# schematic_Eload.net
KiCad netlist of a schematic drawn in Altium Designer
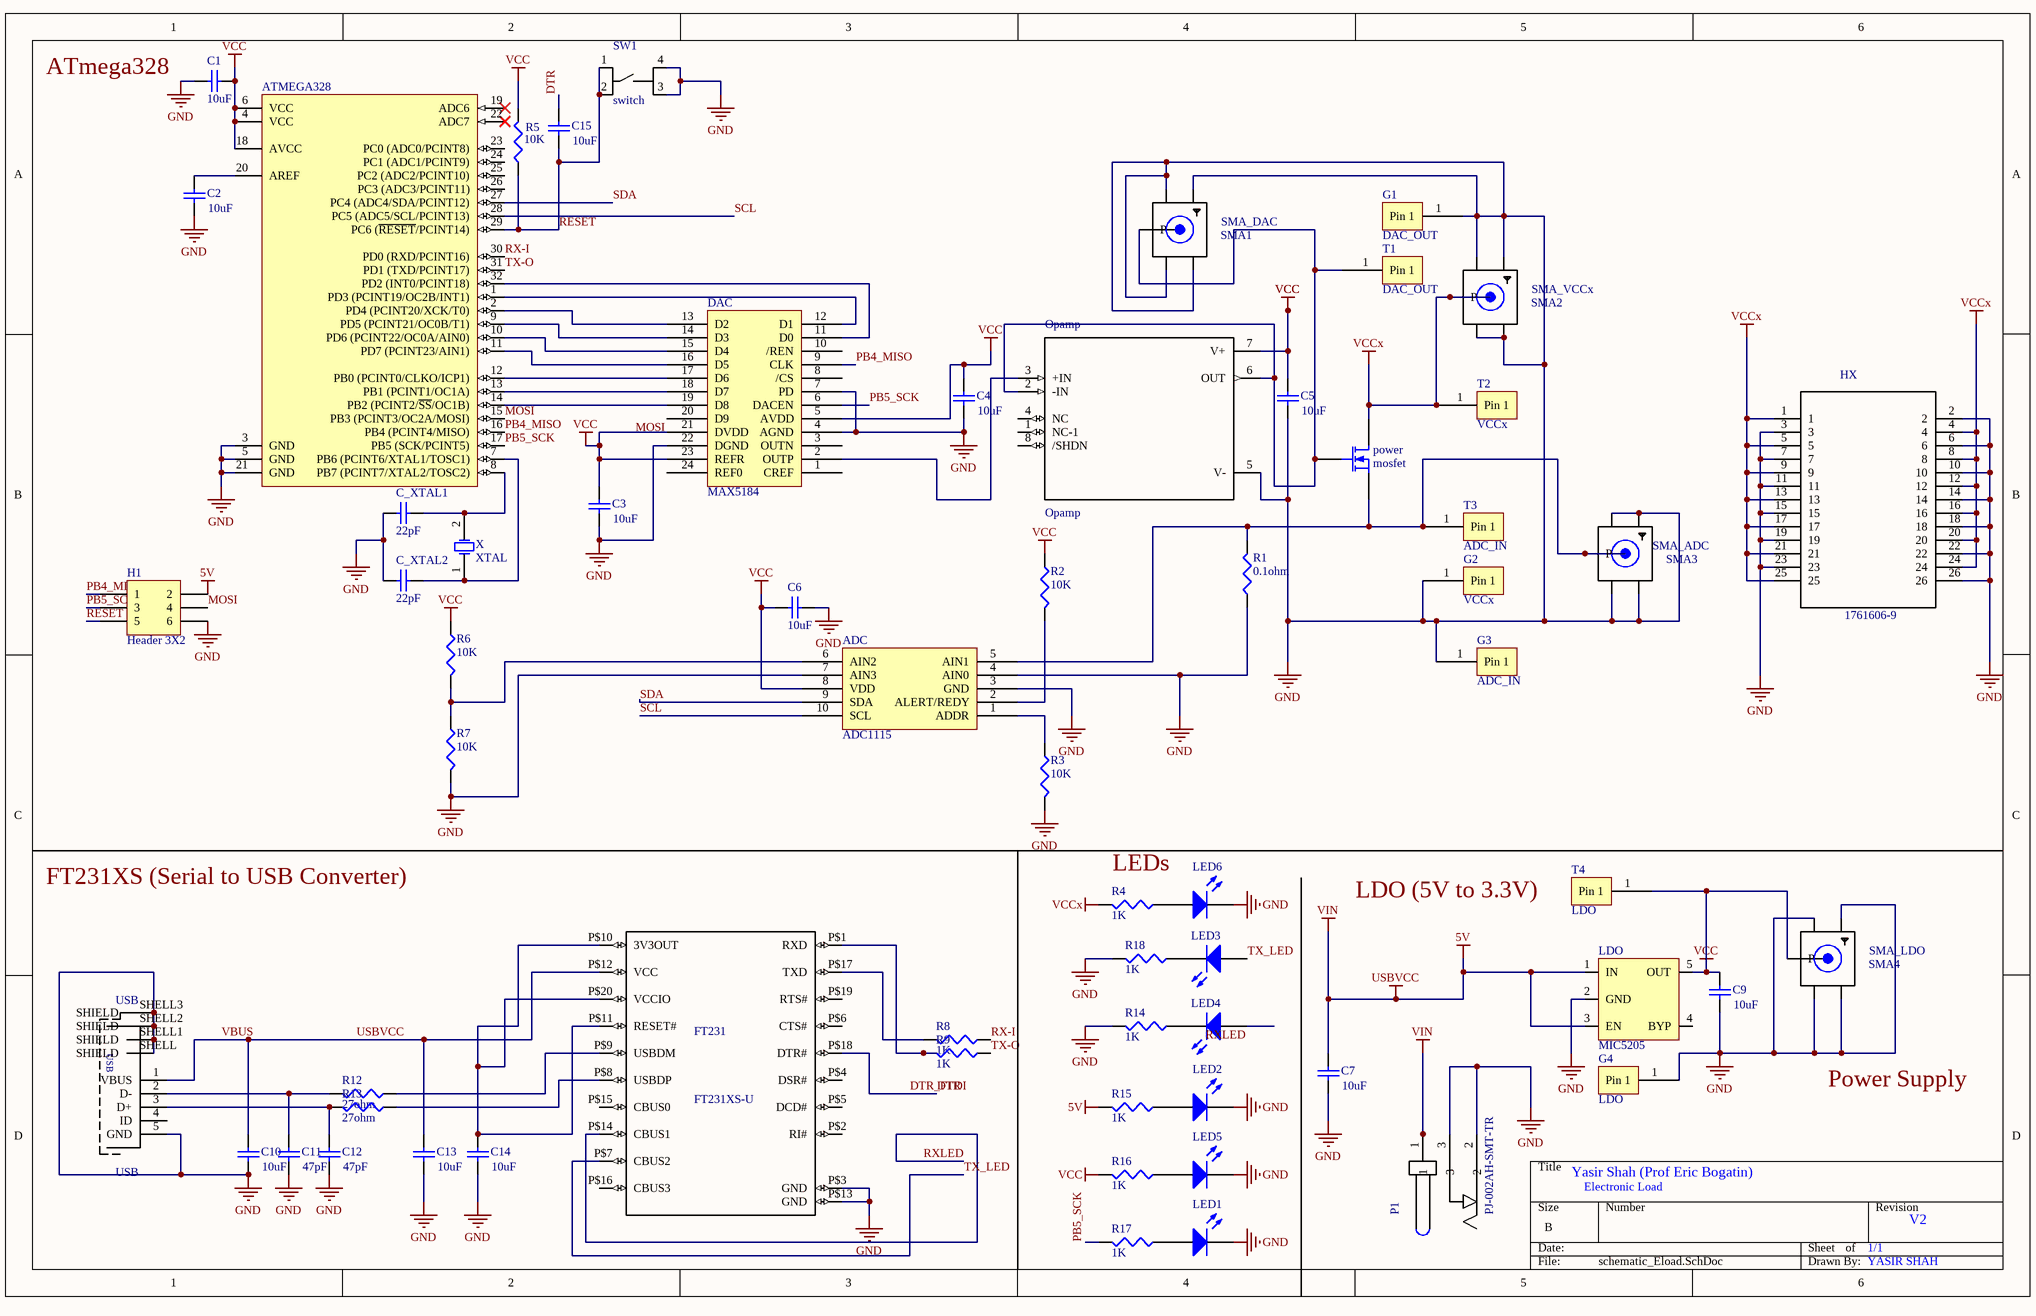
[diagram p0: schematic_Eload.SchDoc]

(export (version "E")
  (design (tool "Eeschema 10.0.6"))
  (components
    (comp (ref "ADC")
      (value "ADC1115")
      (footprint "MSOP10")
      (libsource (lib "Schematic_Library") (part "ADC"))
    )
    (comp (ref "ATMEGA328")
      (value "ATmega328-AU")
      (footprint "QFP32P80_900X900X120L60X37N")
      (fields (field (name "PUBLISHER") "Altium Limited"))
      (libsource (lib "Atmel Microcontroller 8-Bit megaAVR") (part "ATmega328-AU"))
    )
    (comp (ref "C1")
      (value "10uF")
      (footprint "CAPC2012X140N")
      (description "Capacitor (Semiconductor SIM Model)")
      (fields (field (name "Comment") "Cap Semi") (field (name "PUBLISHER") "Altium Limited"))
      (libsource (lib "Miscellaneous Devices") (part "Cap Semi"))
    )
    (comp (ref "C2")
      (value "10uF")
      (footprint "CAPC2012X140N")
      (description "Capacitor (Semiconductor SIM Model)")
      (fields (field (name "Comment") "Cap Semi") (field (name "PUBLISHER") "Altium Limited"))
      (libsource (lib "Miscellaneous Devices") (part "Cap Semi"))
    )
    (comp (ref "C3")
      (value "10uF")
      (footprint "CAPC2012X140N")
      (description "Capacitor (Semiconductor SIM Model)")
      (fields (field (name "Comment") "Cap Semi") (field (name "PUBLISHER") "Altium Limited"))
      (libsource (lib "Miscellaneous Devices") (part "Cap Semi"))
    )
    (comp (ref "C4")
      (value "10uF")
      (footprint "CAPC2012X140N")
      (description "Capacitor (Semiconductor SIM Model)")
      (fields (field (name "Comment") "Cap Semi") (field (name "PUBLISHER") "Altium Limited"))
      (libsource (lib "Miscellaneous Devices") (part "Cap Semi"))
    )
    (comp (ref "C5")
      (value "10uF")
      (footprint "CAPC2012X140N")
      (description "Capacitor (Semiconductor SIM Model)")
      (fields (field (name "Comment") "Cap Semi") (field (name "PUBLISHER") "Altium Limited"))
      (libsource (lib "Miscellaneous Devices") (part "Cap Semi"))
    )
    (comp (ref "C6")
      (value "10uF")
      (footprint "CAPC2012X140N")
      (description "Capacitor (Semiconductor SIM Model)")
      (fields (field (name "Comment") "Cap Semi") (field (name "PUBLISHER") "Altium Limited"))
      (libsource (lib "Miscellaneous Devices") (part "Cap Semi"))
    )
    (comp (ref "C7")
      (value "10uF")
      (footprint "CAPC2012X140N")
      (description "Capacitor (Semiconductor SIM Model)")
      (fields (field (name "Comment") "Cap Semi") (field (name "PUBLISHER") "Altium Limited"))
      (libsource (lib "Miscellaneous Devices") (part "Cap Semi"))
    )
    (comp (ref "C9")
      (value "10uF")
      (footprint "CAPC2012X140N")
      (description "Capacitor (Semiconductor SIM Model)")
      (fields (field (name "Comment") "Cap Semi") (field (name "PUBLISHER") "Altium Limited"))
      (libsource (lib "Miscellaneous Devices") (part "Cap Semi"))
    )
    (comp (ref "C10")
      (value "10uF")
      (footprint "CAPC2012X140N")
      (description "Capacitor (Semiconductor SIM Model)")
      (fields (field (name "Comment") "Cap Semi") (field (name "PUBLISHER") "Altium Limited"))
      (libsource (lib "Miscellaneous Devices") (part "Cap Semi"))
    )
    (comp (ref "C11")
      (value "47pF")
      (footprint "CAPC2012X140N")
      (description "Capacitor (Semiconductor SIM Model)")
      (fields (field (name "Comment") "Cap Semi") (field (name "PUBLISHER") "Altium Limited"))
      (libsource (lib "Miscellaneous Devices") (part "Cap Semi"))
    )
    (comp (ref "C12")
      (value "47pF")
      (footprint "CAPC2012X140N")
      (description "Capacitor (Semiconductor SIM Model)")
      (fields (field (name "Comment") "Cap Semi") (field (name "PUBLISHER") "Altium Limited"))
      (libsource (lib "Miscellaneous Devices") (part "Cap Semi"))
    )
    (comp (ref "C13")
      (value "10uF")
      (footprint "CAPC2012X140N")
      (description "Capacitor (Semiconductor SIM Model)")
      (fields (field (name "Comment") "Cap Semi") (field (name "PUBLISHER") "Altium Limited"))
      (libsource (lib "Miscellaneous Devices") (part "Cap Semi"))
    )
    (comp (ref "C14")
      (value "10uF")
      (footprint "CAPC2012X140N")
      (description "Capacitor (Semiconductor SIM Model)")
      (fields (field (name "Comment") "Cap Semi") (field (name "PUBLISHER") "Altium Limited"))
      (libsource (lib "Miscellaneous Devices") (part "Cap Semi"))
    )
    (comp (ref "C15")
      (value "10uF")
      (footprint "CAPC2012X140N")
      (description "Capacitor (Semiconductor SIM Model)")
      (fields (field (name "Comment") "Cap Semi") (field (name "PUBLISHER") "Altium Limited"))
      (libsource (lib "Miscellaneous Devices") (part "Cap Semi"))
    )
    (comp (ref "C_XTAL1")
      (value "22pF")
      (footprint "CAPC2012X140N")
      (description "Capacitor (Semiconductor SIM Model)")
      (fields (field (name "Comment") "Cap Semi") (field (name "PUBLISHER") "Altium Limited"))
      (libsource (lib "Miscellaneous Devices") (part "Cap Semi"))
    )
    (comp (ref "C_XTAL2")
      (value "22pF")
      (footprint "CAPC2012X140N")
      (description "Capacitor (Semiconductor SIM Model)")
      (fields (field (name "Comment") "Cap Semi") (field (name "PUBLISHER") "Altium Limited"))
      (libsource (lib "Miscellaneous Devices") (part "Cap Semi"))
    )
    (comp (ref "DAC")
      (value "MAX5184")
      (footprint "21-0055H_24")
      (libsource (lib "Schematic_Library") (part "MAX5184"))
    )
    (comp (ref "FT231")
      (value "FT231XS-U")
      (footprint "SSOP20_FT231XS-U(Primary)")
      (description "USB Full Speed to Full Handshake UART with USB Charger Detection, SSOP-20")
      (fields (field (name "MF") "FTDI,"))
      (libsource (lib "FT231XS-U") (part "FT231XS-U"))
    )
    (comp (ref "G1")
      (value "DAC_OUT")
      (footprint "1Pin Header")
      (libsource (lib "SchematicLibrary") (part "1Pin Header"))
    )
    (comp (ref "G2") (value "VCCx") (footprint "1Pin Header") (libsource (lib "") (part "1Pin Header_1")))
    (comp (ref "G3") (value "ADC_IN") (footprint "1Pin Header") (libsource (lib "") (part "1Pin Header_1")))
    (comp (ref "G4")
      (value "LDO")
      (footprint "1Pin Header")
      (libsource (lib "SchematicLibrary") (part "1Pin Header"))
    )
    (comp (ref "H1")
      (value "Header 3X2")
      (footprint "HDR2X3")
      (description "Header, 3-Pin, Dual row")
      (fields (field (name "PUBLISHER") "Altium Limited"))
      (libsource (lib "Miscellaneous Connectors") (part "Header 3X2"))
    )
    (comp (ref "HX")
      (value "1761606-9")
      (footprint "TYCO_1761606-9")
      (description "Header, Pin, Idc, Amp-Latch, 26 Pos, Low Profile, Pcb, Vertical, Black")
      (fields (field (name "MF") "TE Connectivity"))
      (libsource (lib "1761606-9") (part "1761606-9"))
    )
    (comp (ref "LDO") (value "MIC5205") (footprint "SOT23-5") (libsource (lib "CUno_2_2") (part "MIC5205")))
    (comp (ref "LED1")
      (value "LED2")
      (footprint "C1206")
      (description "Typical RED, GREEN, YELLOW, AMBER GaAs LED")
      (fields (field (name "PUBLISHER") "Altium Limited"))
      (libsource (lib "Miscellaneous Devices") (part "LED2"))
    )
    (comp (ref "LED2")
      (value "LED2")
      (footprint "C1206")
      (description "Typical RED, GREEN, YELLOW, AMBER GaAs LED")
      (fields (field (name "PUBLISHER") "Altium Limited"))
      (libsource (lib "Miscellaneous Devices") (part "LED2"))
    )
    (comp (ref "LED3")
      (value "LED2")
      (footprint "C1206")
      (description "Typical RED, GREEN, YELLOW, AMBER GaAs LED")
      (fields (field (name "PUBLISHER") "Altium Limited"))
      (libsource (lib "Miscellaneous Devices") (part "LED2"))
    )
    (comp (ref "LED4")
      (value "LED2")
      (footprint "C1206")
      (description "Typical RED, GREEN, YELLOW, AMBER GaAs LED")
      (fields (field (name "PUBLISHER") "Altium Limited"))
      (libsource (lib "Miscellaneous Devices") (part "LED2"))
    )
    (comp (ref "LED5")
      (value "LED2")
      (footprint "C1206")
      (description "Typical RED, GREEN, YELLOW, AMBER GaAs LED")
      (fields (field (name "PUBLISHER") "Altium Limited"))
      (libsource (lib "Miscellaneous Devices") (part "LED2"))
    )
    (comp (ref "LED6")
      (value "LED2")
      (footprint "C1206")
      (description "Typical RED, GREEN, YELLOW, AMBER GaAs LED")
      (fields (field (name "PUBLISHER") "Altium Limited"))
      (libsource (lib "Miscellaneous Devices") (part "LED2"))
    )
    (comp (ref "Opamp")
      (value "Opamp")
      (footprint "SOP65P490X110-8N")
      (description "LTC6269 - Dual 500MHz Ultra-Low Bias Current FET Input Op Amp")
      (fields (field (name "MF") "Linear Technology") (field (name "MP") "LTC6269IMS8E#PBF"))
      (libsource (lib "LTC6269IMS8E_PBF") (part "LTC6269IMS8E#PBF"))
    )
    (comp (ref "P1")
      (value "PJ-002AH-SMT-TR")
      (footprint "CUI_PJ-002AH-SMT-TR")
      (description "24 VDC 5 A Surface Mount Unshielded 2 Conductors 3 Contacts Male Power Jack")
      (fields (field (name "MF") "CUI"))
      (libsource (lib "PJ-002AH-SMT-TR") (part "PJ-002AH-SMT-TR"))
    )
    (comp (ref "power")
      (value "mosfet")
      (footprint "E3")
      (description "N-Channel MOSFET")
      (fields (field (name "PUBLISHER") "Altium Limited"))
      (libsource (lib "Miscellaneous Devices") (part "MOSFET-N"))
    )
    (comp (ref "R1")
      (value "0.1ohm")
      (footprint "RESC3216X65")
      (description "Resistor")
      (fields (field (name "PUBLISHER") "Altium Limited"))
      (libsource (lib "Miscellaneous Devices") (part "Res3"))
    )
    (comp (ref "R2")
      (value "10K")
      (footprint "RESC2012X70")
      (description "Resistor")
      (fields (field (name "Comment") "Res3") (field (name "PUBLISHER") "Altium Limited"))
      (libsource (lib "Miscellaneous Devices") (part "Res3"))
    )
    (comp (ref "R3")
      (value "10K")
      (footprint "RESC2012X70")
      (description "Resistor")
      (fields (field (name "Comment") "Res3") (field (name "PUBLISHER") "Altium Limited"))
      (libsource (lib "Miscellaneous Devices") (part "Res3"))
    )
    (comp (ref "R4")
      (value "1K")
      (footprint "RESC2012X70")
      (description "Resistor")
      (fields (field (name "Comment") "Res3") (field (name "PUBLISHER") "Altium Limited"))
      (libsource (lib "Miscellaneous Devices") (part "Res3"))
    )
    (comp (ref "R5")
      (value "10K")
      (footprint "RESC2012X70")
      (description "Resistor")
      (fields (field (name "Comment") "Res3") (field (name "PUBLISHER") "Altium Limited"))
      (libsource (lib "Miscellaneous Devices") (part "Res3"))
    )
    (comp (ref "R6")
      (value "10K")
      (footprint "RESC2012X70")
      (description "Resistor")
      (fields (field (name "Comment") "Res3") (field (name "PUBLISHER") "Altium Limited"))
      (libsource (lib "Miscellaneous Devices") (part "Res3"))
    )
    (comp (ref "R7")
      (value "10K")
      (footprint "RESC2012X70")
      (description "Resistor")
      (fields (field (name "Comment") "Res3") (field (name "PUBLISHER") "Altium Limited"))
      (libsource (lib "Miscellaneous Devices") (part "Res3"))
    )
    (comp (ref "R8")
      (value "1K")
      (footprint "RESC2012X70")
      (description "Resistor")
      (fields (field (name "Comment") "Res3") (field (name "PUBLISHER") "Altium Limited"))
      (libsource (lib "Miscellaneous Devices") (part "Res3"))
    )
    (comp (ref "R9")
      (value "1K")
      (footprint "RESC2012X70")
      (description "Resistor")
      (fields (field (name "Comment") "Res3") (field (name "PUBLISHER") "Altium Limited"))
      (libsource (lib "Miscellaneous Devices") (part "Res3"))
    )
    (comp (ref "R12")
      (value "27ohm")
      (footprint "RESC2012X70")
      (description "Resistor")
      (fields (field (name "Comment") "Res3") (field (name "PUBLISHER") "Altium Limited"))
      (libsource (lib "Miscellaneous Devices") (part "Res3"))
    )
    (comp (ref "R13")
      (value "27ohm")
      (footprint "RESC2012X70")
      (description "Resistor")
      (fields (field (name "Comment") "Res3") (field (name "PUBLISHER") "Altium Limited"))
      (libsource (lib "Miscellaneous Devices") (part "Res3"))
    )
    (comp (ref "R14")
      (value "1K")
      (footprint "RESC2012X70")
      (description "Resistor")
      (fields (field (name "Comment") "Res3") (field (name "PUBLISHER") "Altium Limited"))
      (libsource (lib "Miscellaneous Devices") (part "Res3"))
    )
    (comp (ref "R15")
      (value "1K")
      (footprint "RESC2012X70")
      (description "Resistor")
      (fields (field (name "Comment") "Res3") (field (name "PUBLISHER") "Altium Limited"))
      (libsource (lib "Miscellaneous Devices") (part "Res3"))
    )
    (comp (ref "R16")
      (value "1K")
      (footprint "RESC2012X70")
      (description "Resistor")
      (fields (field (name "Comment") "Res3") (field (name "PUBLISHER") "Altium Limited"))
      (libsource (lib "Miscellaneous Devices") (part "Res3"))
    )
    (comp (ref "R17")
      (value "1K")
      (footprint "RESC2012X70")
      (description "Resistor")
      (fields (field (name "Comment") "Res3") (field (name "PUBLISHER") "Altium Limited"))
      (libsource (lib "Miscellaneous Devices") (part "Res3"))
    )
    (comp (ref "R18")
      (value "1K")
      (footprint "RESC2012X70")
      (description "Resistor")
      (fields (field (name "Comment") "Res3") (field (name "PUBLISHER") "Altium Limited"))
      (libsource (lib "Miscellaneous Devices") (part "Res3"))
    )
    (comp (ref "SMA_ADC")
      (value "SMA3")
      (footprint "ADAFRUIT_1865_1865(Primary)")
      (description "Edge-Launch SMA Connector for 1.6mm / 0.062 Thick PCBs")
      (fields (field (name "MP") "1865") (field (name "MF") "Keystone"))
      (libsource (lib "1865") (part "1865"))
    )
    (comp (ref "SMA_DAC")
      (value "SMA1")
      (footprint "ADAFRUIT_1865_1865(Primary)")
      (description "Edge-Launch SMA Connector for 1.6mm / 0.062 Thick PCBs")
      (fields (field (name "MP") "1865") (field (name "MF") "Keystone"))
      (libsource (lib "1865") (part "1865"))
    )
    (comp (ref "SMA_LDO")
      (value "SMA4")
      (footprint "ADAFRUIT_1865_1865(Primary)")
      (description "Edge-Launch SMA Connector for 1.6mm / 0.062 Thick PCBs")
      (fields (field (name "MP") "1865") (field (name "MF") "Keystone"))
      (libsource (lib "1865") (part "1865"))
    )
    (comp (ref "SMA_VCCx")
      (value "SMA2")
      (footprint "ADAFRUIT_1865_1865(Primary)")
      (description "Edge-Launch SMA Connector for 1.6mm / 0.062 Thick PCBs")
      (fields (field (name "MP") "1865") (field (name "MF") "Keystone"))
      (libsource (lib "1865") (part "1865"))
    )
    (comp (ref "SW1")
      (value "switch")
      (footprint "TE_1-1825910-4")
      (description "Switch Tactile OFF (ON) SPST Round Button PC Pins 0.05A 24VDC 100000Cycles 1.56N Thru-Hole Loose")
      (fields (field (name "MF") "TE Connectivity") (field (name "MP") "118259104"))
      (libsource (lib "1-1825910-4") (part "1-1825910-4"))
    )
    (comp (ref "T1") (value "DAC_OUT") (footprint "1Pin Header") (libsource (lib "") (part "1Pin Header_1")))
    (comp (ref "T2") (value "VCCx") (footprint "1Pin Header") (libsource (lib "") (part "1Pin Header_1")))
    (comp (ref "T3") (value "ADC_IN") (footprint "1Pin Header") (libsource (lib "") (part "1Pin Header_1")))
    (comp (ref "T4")
      (value "LDO")
      (footprint "1Pin Header")
      (libsource (lib "SchematicLibrary") (part "1Pin Header"))
    )
    (comp (ref "USB")
      (value "USB")
      (footprint "651005136521_651005136521(Primary)")
      (description "MINI USB A - 5POS Horizontal through hole")
      (fields (field (name "MF") "Wurth Electronics") (field (name "MP") "651005136521"))
      (libsource (lib "651005136521") (part "651005136521"))
    )
    (comp (ref "X")
      (value "XTAL")
      (footprint "R38")
      (description "Crystal Oscillator")
      (fields (field (name "PUBLISHER") "Altium Limited"))
      (libsource (lib "Miscellaneous Devices") (part "XTAL"))
    )
  )
  (nets
    (net (code "1") (name "/DTR") (class "Default")
      (node (ref "C15") (pin "2") (pinfunction "2_2") (pintype "passive"))
      (node (ref "FT231") (pin "P$18") (pinfunction "DTR#_P$18") (pintype "bidirectional"))
    )
    (net (code "2") (name "/MOSI") (class "Default")
      (node (ref "ATMEGA328") (pin "15") (pinfunction "PB3_(PCINT3/OC2A/MOSI)_15") (pintype "bidirectional"))
      (node (ref "DAC") (pin "20") (pinfunction "D9_20") (pintype "passive"))
      (node (ref "H1") (pin "4") (pinfunction "4_4") (pintype "passive"))
    )
    (net (code "3") (name "/PB4_MISO") (class "Default")
      (node (ref "ATMEGA328") (pin "16") (pinfunction "PB4_(PCINT4/MISO)_16") (pintype "bidirectional"))
      (node (ref "DAC") (pin "9") (pinfunction "CLK_9") (pintype "passive"))
      (node (ref "H1") (pin "1") (pinfunction "1_1") (pintype "passive"))
    )
    (net (code "4") (name "/PB5_SCK") (class "Default")
      (node (ref "ATMEGA328") (pin "17") (pinfunction "PB5_(SCK/PCINT5)_17") (pintype "bidirectional"))
      (node (ref "DAC") (pin "6") (pinfunction "DACEN_6") (pintype "passive"))
      (node (ref "H1") (pin "3") (pinfunction "3_3") (pintype "passive"))
      (node (ref "R17") (pin "2") (pinfunction "2_2") (pintype "passive"))
    )
    (net (code "5") (name "/RESET") (class "Default")
      (node (ref "ATMEGA328") (pin "29") (pinfunction "PC6_(~{RESET}/PCINT14)_29") (pintype "bidirectional"))
      (node (ref "C15") (pin "1") (pinfunction "1_1") (pintype "passive"))
      (node (ref "H1") (pin "5") (pinfunction "5_5") (pintype "passive"))
      (node (ref "R5") (pin "1") (pinfunction "1_1") (pintype "passive"))
      (node (ref "SW1") (pin "1") (pinfunction "1_1") (pintype "passive"))
      (node (ref "SW1") (pin "2") (pinfunction "2_2") (pintype "passive"))
    )
    (net (code "6") (name "/RX-I") (class "Default")
      (node (ref "ATMEGA328") (pin "30") (pinfunction "PD0_(RXD/PCINT16)_30") (pintype "bidirectional"))
      (node (ref "R8") (pin "1") (pinfunction "1_1") (pintype "passive"))
    )
    (net (code "7") (name "/RXLED") (class "Default")
      (node (ref "FT231") (pin "P$14") (pinfunction "CBUS1_P$14") (pintype "bidirectional"))
      (node (ref "LED4") (pin "1") (pinfunction "A_1") (pintype "passive"))
    )
    (net (code "8") (name "/SCL") (class "Default")
      (node (ref "ADC") (pin "10") (pinfunction "SCL_10") (pintype "passive"))
      (node (ref "ATMEGA328") (pin "28") (pinfunction "PC5_(ADC5/SCL/PCINT13)_28") (pintype "bidirectional"))
    )
    (net (code "9") (name "/SDA") (class "Default")
      (node (ref "ADC") (pin "9") (pinfunction "SDA_9") (pintype "passive"))
      (node (ref "ATMEGA328") (pin "27") (pinfunction "PC4_(ADC4/SDA/PCINT12)_27") (pintype "bidirectional"))
    )
    (net (code "10") (name "/TX-O") (class "Default")
      (node (ref "ATMEGA328") (pin "31") (pinfunction "PD1_(TXD/PCINT17)_31") (pintype "bidirectional"))
      (node (ref "R9") (pin "1") (pinfunction "1_1") (pintype "passive"))
    )
    (net (code "11") (name "/TX_LED") (class "Default")
      (node (ref "FT231") (pin "P$7") (pinfunction "CBUS2_P$7") (pintype "bidirectional"))
      (node (ref "LED3") (pin "1") (pinfunction "A_1") (pintype "passive"))
    )
    (net (code "12") (name "5V") (class "Default")
      (node (ref "C10") (pin "2") (pinfunction "2_2") (pintype "passive"))
      (node (ref "C13") (pin "2") (pinfunction "2_2") (pintype "passive"))
      (node (ref "C7") (pin "2") (pinfunction "2_2") (pintype "passive"))
      (node (ref "FT231") (pin "P$12") (pinfunction "VCC_P$12") (pintype "bidirectional"))
      (node (ref "H1") (pin "2") (pinfunction "2_2") (pintype "passive"))
      (node (ref "LDO") (pin "1") (pinfunction "IN_1") (pintype "passive"))
      (node (ref "LDO") (pin "3") (pinfunction "EN_3") (pintype "passive"))
      (node (ref "P1") (pin "1") (pinfunction "1_1") (pintype "passive"))
      (node (ref "R15") (pin "2") (pinfunction "2_2") (pintype "passive"))
      (node (ref "USB") (pin "1") (pinfunction "VBUS_1") (pintype "passive"))
    )
    (net (code "13") (name "GND") (class "Default")
      (node (ref "ADC") (pin "3") (pinfunction "GND_3") (pintype "passive"))
      (node (ref "ADC") (pin "4") (pinfunction "AIN0_4") (pintype "passive"))
      (node (ref "ADC") (pin "7") (pinfunction "AIN3_7") (pintype "passive"))
      (node (ref "ATMEGA328") (pin "21") (pinfunction "GND_21") (pintype "power_in"))
      (node (ref "ATMEGA328") (pin "3") (pinfunction "GND_3") (pintype "power_in"))
      (node (ref "ATMEGA328") (pin "5") (pinfunction "GND_5") (pintype "power_in"))
      (node (ref "C1") (pin "2") (pinfunction "2_2") (pintype "passive"))
      (node (ref "C10") (pin "1") (pinfunction "1_1") (pintype "passive"))
      (node (ref "C11") (pin "1") (pinfunction "1_1") (pintype "passive"))
      (node (ref "C12") (pin "1") (pinfunction "1_1") (pintype "passive"))
      (node (ref "C13") (pin "1") (pinfunction "1_1") (pintype "passive"))
      (node (ref "C14") (pin "1") (pinfunction "1_1") (pintype "passive"))
      (node (ref "C2") (pin "1") (pinfunction "1_1") (pintype "passive"))
      (node (ref "C3") (pin "1") (pinfunction "1_1") (pintype "passive"))
      (node (ref "C4") (pin "1") (pinfunction "1_1") (pintype "passive"))
      (node (ref "C5") (pin "1") (pinfunction "1_1") (pintype "passive"))
      (node (ref "C6") (pin "1") (pinfunction "1_1") (pintype "passive"))
      (node (ref "C7") (pin "1") (pinfunction "1_1") (pintype "passive"))
      (node (ref "C9") (pin "1") (pinfunction "1_1") (pintype "passive"))
      (node (ref "C_XTAL1") (pin "2") (pinfunction "2_2") (pintype "passive"))
      (node (ref "C_XTAL2") (pin "2") (pinfunction "2_2") (pintype "passive"))
      (node (ref "DAC") (pin "22") (pinfunction "DGND_22") (pintype "passive"))
      (node (ref "DAC") (pin "4") (pinfunction "AGND_4") (pintype "passive"))
      (node (ref "DAC") (pin "7") (pinfunction "PD_7") (pintype "passive"))
      (node (ref "FT231") (pin "P$13") (pinfunction "GND_P$13") (pintype "bidirectional"))
      (node (ref "FT231") (pin "P$3") (pinfunction "GND_P$3") (pintype "bidirectional"))
      (node (ref "G1") (pin "1") (pinfunction "Pin_1_1") (pintype "passive"))
      (node (ref "G2") (pin "1") (pinfunction "Pin_1_1") (pintype "passive"))
      (node (ref "G3") (pin "1") (pinfunction "Pin_1_1") (pintype "passive"))
      (node (ref "G4") (pin "1") (pinfunction "Pin_1_1") (pintype "passive"))
      (node (ref "H1") (pin "6") (pinfunction "6_6") (pintype "passive"))
      (node (ref "HX") (pin "10") (pinfunction "10_10") (pintype "passive"))
      (node (ref "HX") (pin "11") (pinfunction "11_11") (pintype "passive"))
      (node (ref "HX") (pin "14") (pinfunction "14_14") (pintype "passive"))
      (node (ref "HX") (pin "15") (pinfunction "15_15") (pintype "passive"))
      (node (ref "HX") (pin "18") (pinfunction "18_18") (pintype "passive"))
      (node (ref "HX") (pin "19") (pinfunction "19_19") (pintype "passive"))
      (node (ref "HX") (pin "2") (pinfunction "2_2") (pintype "passive"))
      (node (ref "HX") (pin "22") (pinfunction "22_22") (pintype "passive"))
      (node (ref "HX") (pin "23") (pinfunction "23_23") (pintype "passive"))
      (node (ref "HX") (pin "26") (pinfunction "26_26") (pintype "passive"))
      (node (ref "HX") (pin "3") (pinfunction "3_3") (pintype "passive"))
      (node (ref "HX") (pin "6") (pinfunction "6_6") (pintype "passive"))
      (node (ref "HX") (pin "7") (pinfunction "7_7") (pintype "passive"))
      (node (ref "LDO") (pin "2") (pinfunction "GND_2") (pintype "passive"))
      (node (ref "LED1") (pin "2") (pinfunction "K_2") (pintype "passive"))
      (node (ref "LED2") (pin "2") (pinfunction "K_2") (pintype "passive"))
      (node (ref "LED5") (pin "2") (pinfunction "K_2") (pintype "passive"))
      (node (ref "LED6") (pin "2") (pinfunction "K_2") (pintype "passive"))
      (node (ref "Opamp") (pin "5") (pinfunction "V-_5") (pintype "power_in"))
      (node (ref "P1") (pin "2") (pinfunction "2_2") (pintype "passive"))
      (node (ref "P1") (pin "3") (pinfunction "3_3") (pintype "passive"))
      (node (ref "R1") (pin "1") (pinfunction "1_1") (pintype "passive"))
      (node (ref "R14") (pin "2") (pinfunction "2_2") (pintype "passive"))
      (node (ref "R18") (pin "2") (pinfunction "2_2") (pintype "passive"))
      (node (ref "R3") (pin "2") (pinfunction "2_2") (pintype "passive"))
      (node (ref "R7") (pin "2") (pinfunction "2_2") (pintype "passive"))
      (node (ref "SMA_ADC") (pin "GND1") (pinfunction "GND1_GND1") (pintype "power_in"))
      (node (ref "SMA_ADC") (pin "GND2") (pinfunction "GND2_GND2") (pintype "power_in"))
      (node (ref "SMA_ADC") (pin "GND3") (pinfunction "GND3_GND3") (pintype "power_in"))
      (node (ref "SMA_ADC") (pin "GND4") (pinfunction "GND4_GND4") (pintype "power_in"))
      (node (ref "SMA_DAC") (pin "GND1") (pinfunction "GND1_GND1") (pintype "power_in"))
      (node (ref "SMA_DAC") (pin "GND2") (pinfunction "GND2_GND2") (pintype "power_in"))
      (node (ref "SMA_DAC") (pin "GND3") (pinfunction "GND3_GND3") (pintype "power_in"))
      (node (ref "SMA_DAC") (pin "GND4") (pinfunction "GND4_GND4") (pintype "power_in"))
      (node (ref "SMA_LDO") (pin "GND1") (pinfunction "GND1_GND1") (pintype "power_in"))
      (node (ref "SMA_LDO") (pin "GND2") (pinfunction "GND2_GND2") (pintype "power_in"))
      (node (ref "SMA_LDO") (pin "GND3") (pinfunction "GND3_GND3") (pintype "power_in"))
      (node (ref "SMA_LDO") (pin "GND4") (pinfunction "GND4_GND4") (pintype "power_in"))
      (node (ref "SMA_VCCx") (pin "GND1") (pinfunction "GND1_GND1") (pintype "power_in"))
      (node (ref "SMA_VCCx") (pin "GND2") (pinfunction "GND2_GND2") (pintype "power_in"))
      (node (ref "SMA_VCCx") (pin "GND3") (pinfunction "GND3_GND3") (pintype "power_in"))
      (node (ref "SMA_VCCx") (pin "GND4") (pinfunction "GND4_GND4") (pintype "power_in"))
      (node (ref "SW1") (pin "3") (pinfunction "3_3") (pintype "passive"))
      (node (ref "SW1") (pin "4") (pinfunction "4_4") (pintype "passive"))
      (node (ref "USB") (pin "5") (pinfunction "GND_5") (pintype "passive"))
      (node (ref "USB") (pin "SHELL") (pinfunction "SHIELD_SHELL") (pintype "passive"))
      (node (ref "USB") (pin "SHELL1") (pinfunction "SHIELD_SHELL1") (pintype "passive"))
      (node (ref "USB") (pin "SHELL2") (pinfunction "SHIELD_SHELL2") (pintype "passive"))
      (node (ref "USB") (pin "SHELL3") (pinfunction "SHIELD_SHELL3") (pintype "passive"))
    )
    (net (code "14") (name "Net-(ADC-ADDR)") (class "Default")
      (node (ref "ADC") (pin "1") (pinfunction "ADDR_1") (pintype "passive"))
      (node (ref "R3") (pin "1") (pinfunction "1_1") (pintype "passive"))
    )
    (net (code "15") (name "Net-(ADC-AIN1)") (class "Default")
      (node (ref "ADC") (pin "5") (pinfunction "AIN1_5") (pintype "passive"))
      (node (ref "R1") (pin "2") (pinfunction "2_2") (pintype "passive"))
      (node (ref "SMA_ADC") (pin "P") (pinfunction "P_P") (pintype "bidirectional"))
      (node (ref "T3") (pin "1") (pinfunction "Pin_1_1") (pintype "passive"))
      (node (ref "power") (pin "3") (pinfunction "S_3") (pintype "passive"))
    )
    (net (code "16") (name "Net-(ADC-AIN2)") (class "Default")
      (node (ref "ADC") (pin "6") (pinfunction "AIN2_6") (pintype "passive"))
      (node (ref "R6") (pin "2") (pinfunction "2_2") (pintype "passive"))
      (node (ref "R7") (pin "1") (pinfunction "1_1") (pintype "passive"))
    )
    (net (code "17") (name "Net-(ADC-ALERT{slash}REDY)") (class "Default")
      (node (ref "ADC") (pin "2") (pinfunction "ALERT/REDY_2") (pintype "passive"))
      (node (ref "R2") (pin "2") (pinfunction "2_2") (pintype "passive"))
    )
    (net (code "18") (name "Net-(ATMEGA328-AREF)") (class "Default")
      (node (ref "ATMEGA328") (pin "20") (pinfunction "AREF_20") (pintype "passive"))
      (node (ref "C2") (pin "2") (pinfunction "2_2") (pintype "passive"))
    )
    (net (code "19") (name "Net-(ATMEGA328-PB0_(PCINT0{slash}CLKO{slash}ICP1))") (class "Default")
      (node (ref "ATMEGA328") (pin "12") (pinfunction "PB0_(PCINT0/CLKO/ICP1)_12") (pintype "bidirectional"))
      (node (ref "DAC") (pin "17") (pinfunction "D6_17") (pintype "passive"))
    )
    (net (code "20") (name "Net-(ATMEGA328-PB1_(PCINT1{slash}OC1A))") (class "Default")
      (node (ref "ATMEGA328") (pin "13") (pinfunction "PB1_(PCINT1/OC1A)_13") (pintype "bidirectional"))
      (node (ref "DAC") (pin "18") (pinfunction "D7_18") (pintype "passive"))
    )
    (net (code "21") (name "Net-(ATMEGA328-PB2_(PCINT2{slash}~{SS}{slash}OC1B))") (class "Default")
      (node (ref "ATMEGA328") (pin "14") (pinfunction "PB2_(PCINT2/~{SS}/OC1B)_14") (pintype "bidirectional"))
      (node (ref "DAC") (pin "19") (pinfunction "D8_19") (pintype "passive"))
    )
    (net (code "22") (name "Net-(ATMEGA328-PB6_(PCINT6{slash}XTAL1{slash}TOSC1))") (class "Default")
      (node (ref "ATMEGA328") (pin "7") (pinfunction "PB6_(PCINT6/XTAL1/TOSC1)_7") (pintype "bidirectional"))
      (node (ref "C_XTAL2") (pin "1") (pinfunction "1_1") (pintype "passive"))
      (node (ref "X") (pin "1") (pinfunction "OSC1_1") (pintype "passive"))
    )
    (net (code "23") (name "Net-(ATMEGA328-PB7_(PCINT7{slash}XTAL2{slash}TOSC2))") (class "Default")
      (node (ref "ATMEGA328") (pin "8") (pinfunction "PB7_(PCINT7/XTAL2/TOSC2)_8") (pintype "bidirectional"))
      (node (ref "C_XTAL1") (pin "1") (pinfunction "1_1") (pintype "passive"))
      (node (ref "X") (pin "2") (pinfunction "OSC2_2") (pintype "passive"))
    )
    (net (code "24") (name "Net-(ATMEGA328-PD2_(INT0{slash}PCINT18))") (class "Default")
      (node (ref "ATMEGA328") (pin "32") (pinfunction "PD2_(INT0/PCINT18)_32") (pintype "bidirectional"))
      (node (ref "DAC") (pin "11") (pinfunction "D0_11") (pintype "passive"))
    )
    (net (code "25") (name "Net-(ATMEGA328-PD3_(PCINT19{slash}OC2B{slash}INT1))") (class "Default")
      (node (ref "ATMEGA328") (pin "1") (pinfunction "PD3_(PCINT19/OC2B/INT1)_1") (pintype "bidirectional"))
      (node (ref "DAC") (pin "12") (pinfunction "D1_12") (pintype "passive"))
    )
    (net (code "26") (name "Net-(ATMEGA328-PD4_(PCINT20{slash}XCK{slash}T0))") (class "Default")
      (node (ref "ATMEGA328") (pin "2") (pinfunction "PD4_(PCINT20/XCK/T0)_2") (pintype "bidirectional"))
      (node (ref "DAC") (pin "13") (pinfunction "D2_13") (pintype "passive"))
    )
    (net (code "27") (name "Net-(ATMEGA328-PD5_(PCINT21{slash}OC0B{slash}T1))") (class "Default")
      (node (ref "ATMEGA328") (pin "9") (pinfunction "PD5_(PCINT21/OC0B/T1)_9") (pintype "bidirectional"))
      (node (ref "DAC") (pin "14") (pinfunction "D3_14") (pintype "passive"))
    )
    (net (code "28") (name "Net-(ATMEGA328-PD6_(PCINT22{slash}OC0A{slash}AIN0))") (class "Default")
      (node (ref "ATMEGA328") (pin "10") (pinfunction "PD6_(PCINT22/OC0A/AIN0)_10") (pintype "bidirectional"))
      (node (ref "DAC") (pin "15") (pinfunction "D4_15") (pintype "passive"))
    )
    (net (code "29") (name "Net-(ATMEGA328-PD7_(PCINT23{slash}AIN1))") (class "Default")
      (node (ref "ATMEGA328") (pin "11") (pinfunction "PD7_(PCINT23/AIN1)_11") (pintype "bidirectional"))
      (node (ref "DAC") (pin "16") (pinfunction "D5_16") (pintype "passive"))
    )
    (net (code "30") (name "Net-(DAC-OUTP)") (class "Default")
      (node (ref "DAC") (pin "2") (pinfunction "OUTP_2") (pintype "passive"))
      (node (ref "Opamp") (pin "3") (pinfunction "+IN_3") (pintype "input"))
    )
    (net (code "31") (name "Net-(FT231-3V3OUT)") (class "Default")
      (node (ref "C14") (pin "2") (pinfunction "2_2") (pintype "passive"))
      (node (ref "FT231") (pin "P$10") (pinfunction "3V3OUT_P$10") (pintype "bidirectional"))
      (node (ref "FT231") (pin "P$11") (pinfunction "RESET#_P$11") (pintype "bidirectional"))
      (node (ref "FT231") (pin "P$20") (pinfunction "VCCIO_P$20") (pintype "bidirectional"))
    )
    (net (code "32") (name "Net-(FT231-RXD)") (class "Default")
      (node (ref "FT231") (pin "P$1") (pinfunction "RXD_P$1") (pintype "bidirectional"))
      (node (ref "R9") (pin "2") (pinfunction "2_2") (pintype "passive"))
    )
    (net (code "33") (name "Net-(FT231-TXD)") (class "Default")
      (node (ref "FT231") (pin "P$17") (pinfunction "TXD_P$17") (pintype "bidirectional"))
      (node (ref "R8") (pin "2") (pinfunction "2_2") (pintype "passive"))
    )
    (net (code "34") (name "Net-(FT231-USBDM)") (class "Default")
      (node (ref "FT231") (pin "P$9") (pinfunction "USBDM_P$9") (pintype "bidirectional"))
      (node (ref "R12") (pin "1") (pinfunction "1_1") (pintype "passive"))
    )
    (net (code "35") (name "Net-(FT231-USBDP)") (class "Default")
      (node (ref "FT231") (pin "P$8") (pinfunction "USBDP_P$8") (pintype "bidirectional"))
      (node (ref "R13") (pin "1") (pinfunction "1_1") (pintype "passive"))
    )
    (net (code "36") (name "Net-(LED1-A)") (class "Default")
      (node (ref "LED1") (pin "1") (pinfunction "A_1") (pintype "passive"))
      (node (ref "R17") (pin "1") (pinfunction "1_1") (pintype "passive"))
    )
    (net (code "37") (name "Net-(LED2-A)") (class "Default")
      (node (ref "LED2") (pin "1") (pinfunction "A_1") (pintype "passive"))
      (node (ref "R15") (pin "1") (pinfunction "1_1") (pintype "passive"))
    )
    (net (code "38") (name "Net-(LED3-K)") (class "Default")
      (node (ref "LED3") (pin "2") (pinfunction "K_2") (pintype "passive"))
      (node (ref "R18") (pin "1") (pinfunction "1_1") (pintype "passive"))
    )
    (net (code "39") (name "Net-(LED4-K)") (class "Default")
      (node (ref "LED4") (pin "2") (pinfunction "K_2") (pintype "passive"))
      (node (ref "R14") (pin "1") (pinfunction "1_1") (pintype "passive"))
    )
    (net (code "40") (name "Net-(LED5-A)") (class "Default")
      (node (ref "LED5") (pin "1") (pinfunction "A_1") (pintype "passive"))
      (node (ref "R16") (pin "1") (pinfunction "1_1") (pintype "passive"))
    )
    (net (code "41") (name "Net-(LED6-A)") (class "Default")
      (node (ref "LED6") (pin "1") (pinfunction "A_1") (pintype "passive"))
      (node (ref "R4") (pin "1") (pinfunction "1_1") (pintype "passive"))
    )
    (net (code "42") (name "Net-(Opamp--IN)") (class "Default")
      (node (ref "Opamp") (pin "2") (pinfunction "-IN_2") (pintype "input"))
      (node (ref "Opamp") (pin "6") (pinfunction "OUT_6") (pintype "output"))
      (node (ref "SMA_DAC") (pin "P") (pinfunction "P_P") (pintype "bidirectional"))
      (node (ref "T1") (pin "1") (pinfunction "Pin_1_1") (pintype "passive"))
      (node (ref "power") (pin "2") (pinfunction "G_2") (pintype "passive"))
    )
    (net (code "43") (name "Net-(USB-D+)") (class "Default")
      (node (ref "C12") (pin "2") (pinfunction "2_2") (pintype "passive"))
      (node (ref "R13") (pin "2") (pinfunction "2_2") (pintype "passive"))
      (node (ref "USB") (pin "3") (pinfunction "D+_3") (pintype "passive"))
    )
    (net (code "44") (name "Net-(USB-D-)") (class "Default")
      (node (ref "C11") (pin "2") (pinfunction "2_2") (pintype "passive"))
      (node (ref "R12") (pin "2") (pinfunction "2_2") (pintype "passive"))
      (node (ref "USB") (pin "2") (pinfunction "D-_2") (pintype "passive"))
    )
    (net (code "45") (name "VCC") (class "Default")
      (node (ref "ADC") (pin "8") (pinfunction "VDD_8") (pintype "passive"))
      (node (ref "ATMEGA328") (pin "18") (pinfunction "AVCC_18") (pintype "power_in"))
      (node (ref "ATMEGA328") (pin "4") (pinfunction "VCC_4") (pintype "power_in"))
      (node (ref "ATMEGA328") (pin "6") (pinfunction "VCC_6") (pintype "power_in"))
      (node (ref "C1") (pin "1") (pinfunction "1_1") (pintype "passive"))
      (node (ref "C3") (pin "2") (pinfunction "2_2") (pintype "passive"))
      (node (ref "C4") (pin "2") (pinfunction "2_2") (pintype "passive"))
      (node (ref "C5") (pin "2") (pinfunction "2_2") (pintype "passive"))
      (node (ref "C6") (pin "2") (pinfunction "2_2") (pintype "passive"))
      (node (ref "C9") (pin "2") (pinfunction "2_2") (pintype "passive"))
      (node (ref "DAC") (pin "21") (pinfunction "DVDD_21") (pintype "passive"))
      (node (ref "DAC") (pin "23") (pinfunction "REFR_23") (pintype "passive"))
      (node (ref "DAC") (pin "5") (pinfunction "AVDD_5") (pintype "passive"))
      (node (ref "LDO") (pin "5") (pinfunction "OUT_5") (pintype "passive"))
      (node (ref "Opamp") (pin "7") (pinfunction "V+_7") (pintype "power_in"))
      (node (ref "R16") (pin "2") (pinfunction "2_2") (pintype "passive"))
      (node (ref "R2") (pin "1") (pinfunction "1_1") (pintype "passive"))
      (node (ref "R5") (pin "2") (pinfunction "2_2") (pintype "passive"))
      (node (ref "R6") (pin "1") (pinfunction "1_1") (pintype "passive"))
      (node (ref "SMA_LDO") (pin "P") (pinfunction "P_P") (pintype "bidirectional"))
      (node (ref "T4") (pin "1") (pinfunction "Pin_1_1") (pintype "passive"))
    )
    (net (code "46") (name "VCCx") (class "Default")
      (node (ref "HX") (pin "1") (pinfunction "1_1") (pintype "passive"))
      (node (ref "HX") (pin "12") (pinfunction "12_12") (pintype "passive"))
      (node (ref "HX") (pin "13") (pinfunction "13_13") (pintype "passive"))
      (node (ref "HX") (pin "16") (pinfunction "16_16") (pintype "passive"))
      (node (ref "HX") (pin "17") (pinfunction "17_17") (pintype "passive"))
      (node (ref "HX") (pin "20") (pinfunction "20_20") (pintype "passive"))
      (node (ref "HX") (pin "21") (pinfunction "21_21") (pintype "passive"))
      (node (ref "HX") (pin "24") (pinfunction "24_24") (pintype "passive"))
      (node (ref "HX") (pin "25") (pinfunction "25_25") (pintype "passive"))
      (node (ref "HX") (pin "4") (pinfunction "4_4") (pintype "passive"))
      (node (ref "HX") (pin "5") (pinfunction "5_5") (pintype "passive"))
      (node (ref "HX") (pin "8") (pinfunction "8_8") (pintype "passive"))
      (node (ref "HX") (pin "9") (pinfunction "9_9") (pintype "passive"))
      (node (ref "R4") (pin "2") (pinfunction "2_2") (pintype "passive"))
      (node (ref "SMA_VCCx") (pin "P") (pinfunction "P_P") (pintype "bidirectional"))
      (node (ref "T2") (pin "1") (pinfunction "Pin_1_1") (pintype "passive"))
      (node (ref "power") (pin "1") (pinfunction "D_1") (pintype "passive"))
    )
    (net (code "47") (name "unconnected-(ATMEGA328-ADC6-Pad19)") (class "Default")
      (node (ref "ATMEGA328") (pin "19") (pinfunction "ADC6_19") (pintype "input+no_connect"))
    )
    (net (code "48") (name "unconnected-(ATMEGA328-ADC7-Pad22)") (class "Default")
      (node (ref "ATMEGA328") (pin "22") (pinfunction "ADC7_22") (pintype "input+no_connect"))
    )
    (net (code "49") (name "unconnected-(ATMEGA328-PC0_(ADC0{slash}PCINT8)-Pad23)") (class "Default")
      (node (ref "ATMEGA328") (pin "23") (pinfunction "PC0_(ADC0/PCINT8)_23") (pintype "bidirectional"))
    )
    (net (code "50") (name "unconnected-(ATMEGA328-PC1_(ADC1{slash}PCINT9)-Pad24)") (class "Default")
      (node (ref "ATMEGA328") (pin "24") (pinfunction "PC1_(ADC1/PCINT9)_24") (pintype "bidirectional"))
    )
    (net (code "51") (name "unconnected-(ATMEGA328-PC2_(ADC2{slash}PCINT10)-Pad25)") (class "Default")
      (node (ref "ATMEGA328") (pin "25") (pinfunction "PC2_(ADC2/PCINT10)_25") (pintype "bidirectional"))
    )
    (net (code "52") (name "unconnected-(ATMEGA328-PC3_(ADC3{slash}PCINT11)-Pad26)") (class "Default")
      (node (ref "ATMEGA328") (pin "26") (pinfunction "PC3_(ADC3/PCINT11)_26") (pintype "bidirectional"))
    )
    (net (code "53") (name "unconnected-(DAC-CREF-Pad1)") (class "Default")
      (node (ref "DAC") (pin "1") (pinfunction "CREF_1") (pintype "passive"))
    )
    (net (code "54") (name "unconnected-(DAC-OUTN-Pad3)") (class "Default")
      (node (ref "DAC") (pin "3") (pinfunction "OUTN_3") (pintype "passive"))
    )
    (net (code "55") (name "unconnected-(DAC-REF0-Pad24)") (class "Default")
      (node (ref "DAC") (pin "24") (pinfunction "REF0_24") (pintype "passive"))
    )
    (net (code "56") (name "unconnected-(DAC-{slash}CS-Pad8)") (class "Default")
      (node (ref "DAC") (pin "8") (pinfunction "/CS_8") (pintype "passive"))
    )
    (net (code "57") (name "unconnected-(DAC-{slash}REN-Pad10)") (class "Default")
      (node (ref "DAC") (pin "10") (pinfunction "/REN_10") (pintype "passive"))
    )
    (net (code "58") (name "unconnected-(FT231-CBUS0-PadP$15)") (class "Default")
      (node (ref "FT231") (pin "P$15") (pinfunction "CBUS0_P$15") (pintype "bidirectional"))
    )
    (net (code "59") (name "unconnected-(FT231-CBUS3-PadP$16)") (class "Default")
      (node (ref "FT231") (pin "P$16") (pinfunction "CBUS3_P$16") (pintype "bidirectional"))
    )
    (net (code "60") (name "unconnected-(FT231-CTS#-PadP$6)") (class "Default")
      (node (ref "FT231") (pin "P$6") (pinfunction "CTS#_P$6") (pintype "bidirectional"))
    )
    (net (code "61") (name "unconnected-(FT231-DCD#-PadP$5)") (class "Default")
      (node (ref "FT231") (pin "P$5") (pinfunction "DCD#_P$5") (pintype "bidirectional"))
    )
    (net (code "62") (name "unconnected-(FT231-DSR#-PadP$4)") (class "Default")
      (node (ref "FT231") (pin "P$4") (pinfunction "DSR#_P$4") (pintype "bidirectional"))
    )
    (net (code "63") (name "unconnected-(FT231-RI#-PadP$2)") (class "Default")
      (node (ref "FT231") (pin "P$2") (pinfunction "RI#_P$2") (pintype "bidirectional"))
    )
    (net (code "64") (name "unconnected-(FT231-RTS#-PadP$19)") (class "Default")
      (node (ref "FT231") (pin "P$19") (pinfunction "RTS#_P$19") (pintype "bidirectional"))
    )
    (net (code "65") (name "unconnected-(LDO-BYP-Pad4)") (class "Default")
      (node (ref "LDO") (pin "4") (pinfunction "BYP_4") (pintype "passive"))
    )
    (net (code "66") (name "unconnected-(Opamp-NC-1-Pad1)") (class "Default")
      (node (ref "Opamp") (pin "1") (pinfunction "NC-1_1") (pintype "bidirectional"))
    )
    (net (code "67") (name "unconnected-(Opamp-NC-Pad4)") (class "Default")
      (node (ref "Opamp") (pin "4") (pinfunction "NC_4") (pintype "bidirectional"))
    )
    (net (code "68") (name "unconnected-(Opamp-{slash}SHDN-Pad8)") (class "Default")
      (node (ref "Opamp") (pin "8") (pinfunction "/SHDN_8") (pintype "bidirectional"))
    )
    (net (code "69") (name "unconnected-(USB-ID-Pad4)") (class "Default")
      (node (ref "USB") (pin "4") (pinfunction "ID_4") (pintype "passive"))
    )
  )
)
